# FLK01B.net
KiCad netlist of a schematic drawn in EAGLE
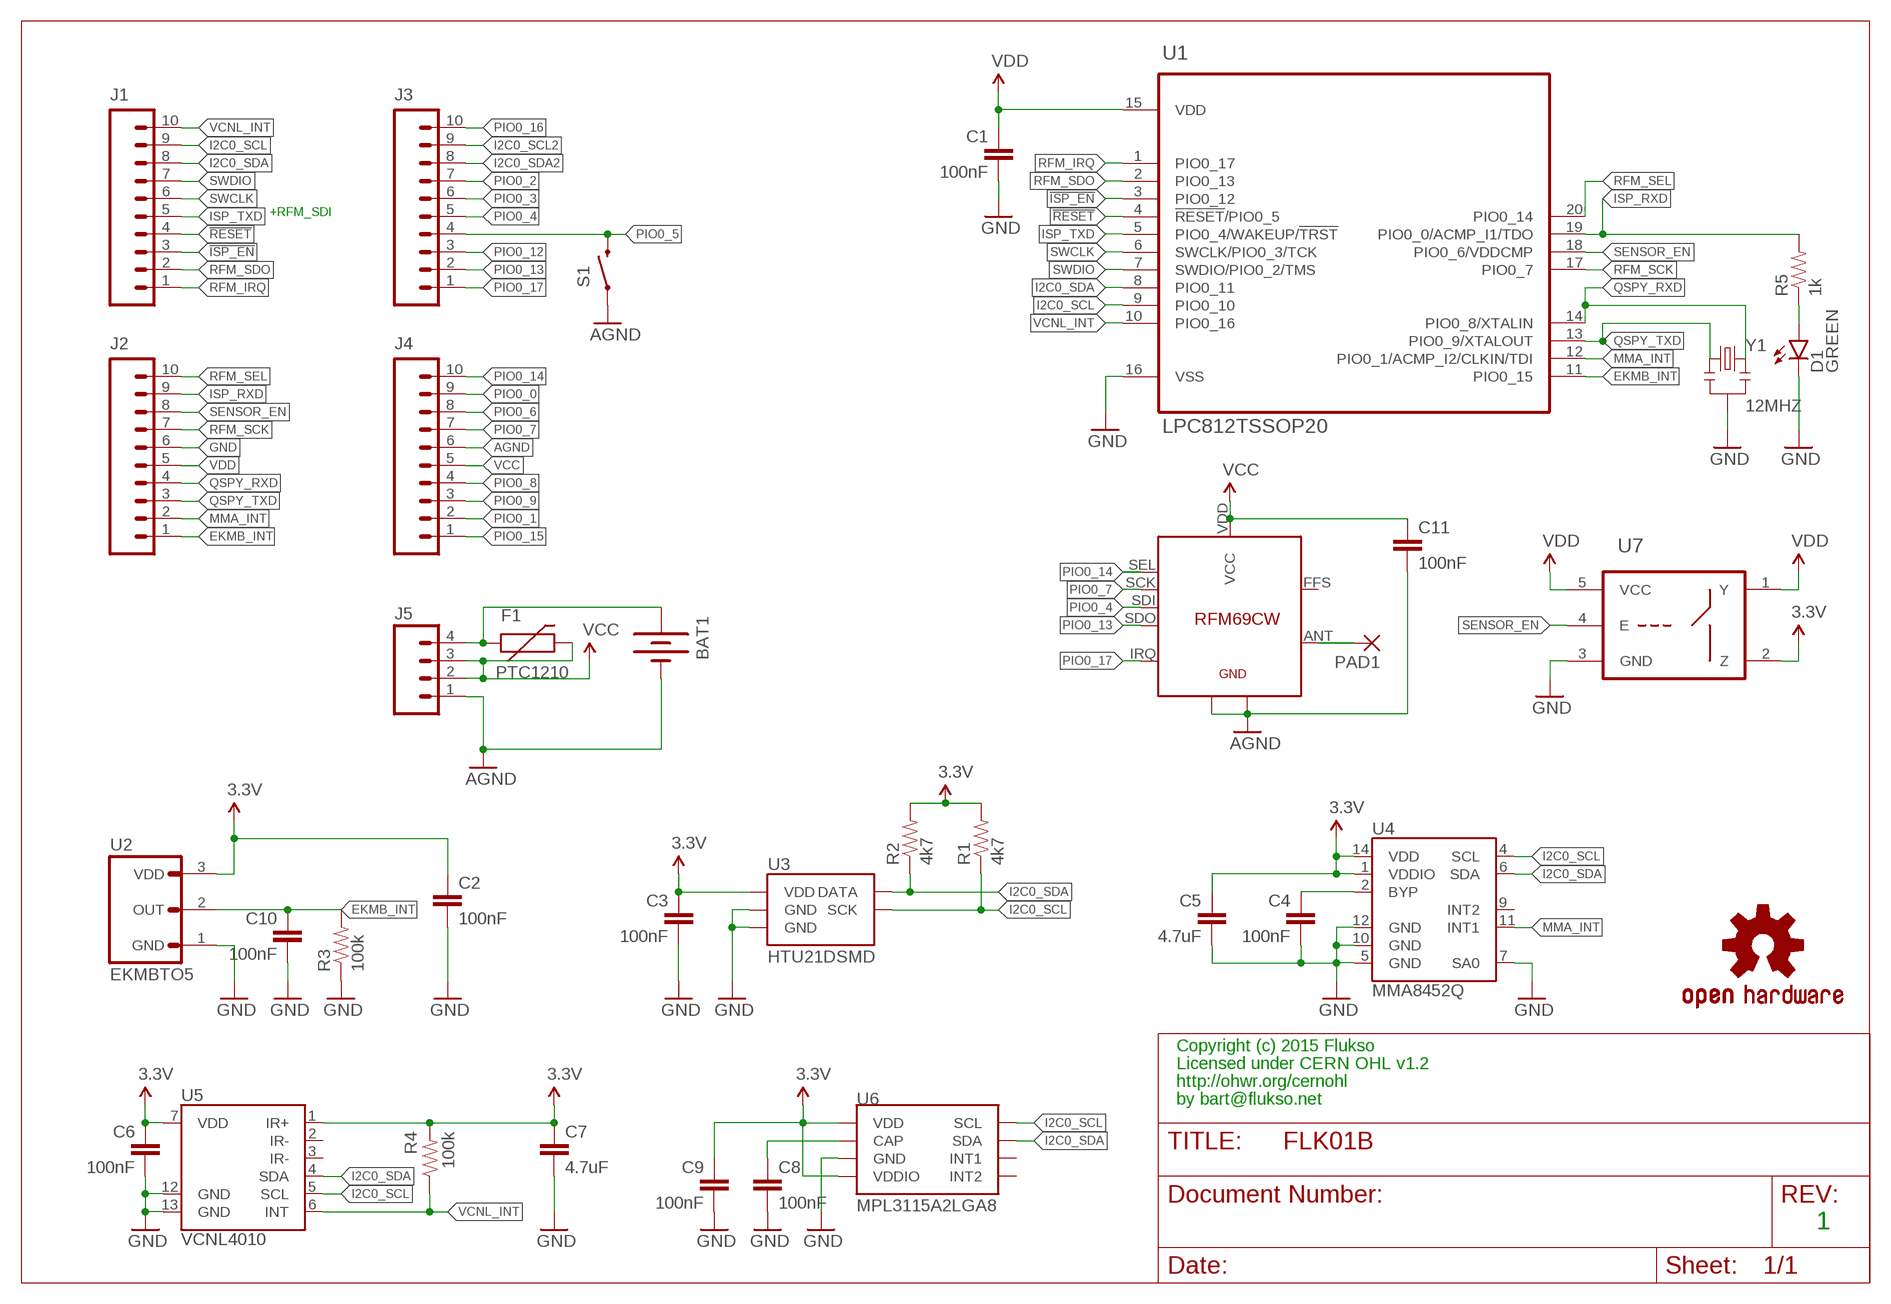
[diagram p0: schematic, sheet 1]

(export (version "E")
  (design (tool "Eeschema 10.0.6"))
  (components
    (comp (ref "BAT1")
      (value "BATTERY245PTH")
      (footprint "eagle-import:BATTCON_245MM_PTH")
      (libsource (lib "eagle-import") (part "BATTERY245PTH"))
    )
    (comp (ref "C1")
      (value "100nF")
      (footprint "eagle-import:0402-CAP")
      (libsource (lib "eagle-import") (part "CAP0402-CAP"))
    )
    (comp (ref "C2")
      (value "100nF")
      (footprint "eagle-import:0402-CAP")
      (libsource (lib "eagle-import") (part "CAP0402-CAP"))
    )
    (comp (ref "C3")
      (value "100nF")
      (footprint "eagle-import:0402-CAP")
      (libsource (lib "eagle-import") (part "CAP0402-CAP"))
    )
    (comp (ref "C4")
      (value "100nF")
      (footprint "eagle-import:0402-CAP")
      (libsource (lib "eagle-import") (part "CAP0402-CAP"))
    )
    (comp (ref "C5")
      (value "4.7uF")
      (footprint "eagle-import:C0805K")
      (libsource (lib "eagle-import") (part "CAP0805-CAP"))
    )
    (comp (ref "C6")
      (value "100nF")
      (footprint "eagle-import:0402-CAP")
      (libsource (lib "eagle-import") (part "CAP0402-CAP"))
    )
    (comp (ref "C7")
      (value "4.7uF")
      (footprint "eagle-import:C0805K")
      (libsource (lib "eagle-import") (part "CAP0805-CAP"))
    )
    (comp (ref "C8")
      (value "100nF")
      (footprint "eagle-import:0402-CAP")
      (libsource (lib "eagle-import") (part "CAP0402-CAP"))
    )
    (comp (ref "C9")
      (value "100nF")
      (footprint "eagle-import:0402-CAP")
      (libsource (lib "eagle-import") (part "CAP0402-CAP"))
    )
    (comp (ref "C10")
      (value "100nF")
      (footprint "eagle-import:0402-CAP")
      (libsource (lib "eagle-import") (part "CAP0402-CAP"))
    )
    (comp (ref "C11")
      (value "100nF")
      (footprint "eagle-import:0402-CAP")
      (libsource (lib "eagle-import") (part "sparkFun_CAP0402-CAP"))
    )
    (comp (ref "D1")
      (value "GREEN")
      (footprint "eagle-import:LED-0603")
      (libsource (lib "eagle-import") (part "LED-GREEN0603"))
    )
    (comp (ref "F1")
      (value "PTC1210")
      (footprint "eagle-import:1210")
      (libsource (lib "eagle-import") (part "PTC1210"))
    )
    (comp (ref "J1")
      (value "M10SMD_MALE_SHORT")
      (footprint "eagle-import:1X10_SMD_MALE_SHORT")
      (libsource (lib "eagle-import") (part "M10SMD_MALE_SHORT"))
    )
    (comp (ref "J2")
      (value "M10SMD_MALE_SHORT")
      (footprint "eagle-import:1X10_SMD_MALE_SHORT")
      (libsource (lib "eagle-import") (part "M10SMD_MALE_SHORT"))
    )
    (comp (ref "J3")
      (value "M10SMD_FEMALE_SHORT")
      (footprint "eagle-import:1X10_SMD_FEMALE_SHORT")
      (libsource (lib "eagle-import") (part "M10SMD_FEMALE_SHORT"))
    )
    (comp (ref "J4")
      (value "M10SMD_FEMALE_SHORT")
      (footprint "eagle-import:1X10_SMD_FEMALE_SHORT")
      (libsource (lib "eagle-import") (part "M10SMD_FEMALE_SHORT"))
    )
    (comp (ref "J5")
      (value "M041X04_NO_SILK")
      (footprint "eagle-import:1X04_NO_SILK")
      (libsource (lib "eagle-import") (part "M041X04_NO_SILK"))
    )
    (comp (ref "PAD1")
      (value "WIREPAD_1,6/0,8")
      (footprint "eagle-import:WIREPAD_1,6_0,8")
      (libsource (lib "eagle-import") (part "WIREPAD_1,6/0,8"))
    )
    (comp (ref "R1")
      (value "4k7")
      (footprint "eagle-import:0402-RES")
      (libsource (lib "eagle-import") (part "RESISTOR0402-RES"))
    )
    (comp (ref "R2")
      (value "4k7")
      (footprint "eagle-import:0402-RES")
      (libsource (lib "eagle-import") (part "RESISTOR0402-RES"))
    )
    (comp (ref "R3")
      (value "100k")
      (footprint "eagle-import:0402-RES")
      (libsource (lib "eagle-import") (part "RESISTOR0402-RES"))
    )
    (comp (ref "R4")
      (value "100k")
      (footprint "eagle-import:0402-RES")
      (libsource (lib "eagle-import") (part "RESISTOR0402-RES"))
    )
    (comp (ref "R5")
      (value "1k")
      (footprint "eagle-import:0402-RES")
      (libsource (lib "eagle-import") (part "RESISTOR0402-RES"))
    )
    (comp (ref "S1")
      (value "SWITCH-MOMENTARY-2SMD")
      (footprint "eagle-import:TACTILE_SWITCH_SMD")
      (libsource (lib "eagle-import") (part "SWITCH-MOMENTARY-2SMD"))
    )
    (comp (ref "U$3")
      (value "RFM69CW")
      (footprint "eagle-import:RFM69CW")
      (libsource (lib "eagle-import") (part "RFM69CW"))
    )
    (comp (ref "U$7")
      (value "OSHW-LOGOS")
      (footprint "eagle-import:OSHW-LOGO-S")
      (libsource (lib "eagle-import") (part "OSHW-LOGOS"))
    )
    (comp (ref "U1")
      (value "LPC812TSSOP20")
      (footprint "eagle-import:TSSOP20")
      (libsource (lib "eagle-import") (part "LPC812TSSOP20"))
    )
    (comp (ref "U2")
      (value "EKMBTO5")
      (footprint "eagle-import:TO5")
      (libsource (lib "eagle-import") (part "EKMBTO5"))
    )
    (comp (ref "U3")
      (value "HTU21DSMD")
      (footprint "eagle-import:HTU21D")
      (libsource (lib "eagle-import") (part "HTU21DSMD"))
    )
    (comp (ref "U4")
      (value "MMA8452Q")
      (footprint "eagle-import:QFN-16_0.5MM")
      (libsource (lib "eagle-import") (part "MMA8452Q"))
    )
    (comp (ref "U5")
      (value "VCNL4010")
      (footprint "eagle-import:VCNL4010")
      (libsource (lib "eagle-import") (part "VCNL4010"))
    )
    (comp (ref "U6")
      (value "MPL3115A2LGA8")
      (footprint "eagle-import:LGA8")
      (libsource (lib "eagle-import") (part "MPL3115A2LGA8"))
    )
    (comp (ref "U7")
      (value "741G66")
      (footprint "eagle-import:SOT353")
      (libsource (lib "eagle-import") (part "741G66"))
    )
    (comp (ref "Y1")
      (value "12MHZ")
      (footprint "eagle-import:RESONATOR-SMD")
      (libsource (lib "eagle-import") (part "RESONATOR8MHZ"))
    )
  )
  (nets
    (net (code "1") (name "/~{ISP_EN}") (class "Default")
      (node (ref "J1") (pin "3") (pinfunction "3_3") (pintype "passive"))
      (node (ref "U1") (pin "3") (pinfunction "PIO0_12_3") (pintype "bidirectional"))
    )
    (net (code "2") (name "/~{RESET}") (class "Default")
      (node (ref "J1") (pin "4") (pinfunction "4_4") (pintype "passive"))
      (node (ref "U1") (pin "4") (pinfunction "~{RESET}/PIO0_5_4") (pintype "bidirectional"))
    )
    (net (code "3") (name "3.3V") (class "Default")
      (node (ref "C2") (pin "1") (pinfunction "1_1") (pintype "passive"))
      (node (ref "C3") (pin "1") (pinfunction "1_1") (pintype "passive"))
      (node (ref "C5") (pin "1") (pinfunction "1_1") (pintype "passive"))
      (node (ref "C6") (pin "1") (pinfunction "1_1") (pintype "passive"))
      (node (ref "C7") (pin "1") (pinfunction "1_1") (pintype "passive"))
      (node (ref "C9") (pin "1") (pinfunction "1_1") (pintype "passive"))
      (node (ref "R1") (pin "2") (pinfunction "2_2") (pintype "passive"))
      (node (ref "R2") (pin "2") (pinfunction "2_2") (pintype "passive"))
      (node (ref "R4") (pin "2") (pinfunction "2_2") (pintype "passive"))
      (node (ref "U2") (pin "3") (pinfunction "VDD_3") (pintype "power_in"))
      (node (ref "U3") (pin "VDD") (pinfunction "VDD_VDD") (pintype "power_in"))
      (node (ref "U4") (pin "1") (pinfunction "VDDIO_1") (pintype "bidirectional"))
      (node (ref "U4") (pin "14") (pinfunction "VDD_14") (pintype "bidirectional"))
      (node (ref "U5") (pin "1") (pinfunction "IR+_1") (pintype "bidirectional"))
      (node (ref "U5") (pin "7") (pinfunction "VDD_7") (pintype "bidirectional"))
      (node (ref "U6") (pin "1") (pinfunction "VDD_1") (pintype "power_in"))
      (node (ref "U6") (pin "4") (pinfunction "VDDIO_4") (pintype "power_in"))
      (node (ref "U7") (pin "2") (pinfunction "Z_2") (pintype "bidirectional"))
    )
    (net (code "4") (name "AGND") (class "Default")
      (node (ref "BAT1") (pin "2") (pinfunction "-_2") (pintype "power_in"))
      (node (ref "C11") (pin "2") (pinfunction "2_2") (pintype "passive"))
      (node (ref "J4") (pin "6") (pinfunction "6_6") (pintype "passive"))
      (node (ref "J5") (pin "1") (pinfunction "1_1") (pintype "passive"))
      (node (ref "S1") (pin "1") (pinfunction "1_1") (pintype "passive"))
      (node (ref "U$3") (pin "GND1") (pinfunction "GND1_GND1") (pintype "power_in"))
      (node (ref "U$3") (pin "GND2") (pinfunction "GND2_GND2") (pintype "power_in"))
    )
    (net (code "5") (name "EKMB_INT") (class "Default")
      (node (ref "C10") (pin "1") (pinfunction "1_1") (pintype "passive"))
      (node (ref "J2") (pin "1") (pinfunction "1_1") (pintype "passive"))
      (node (ref "R3") (pin "2") (pinfunction "2_2") (pintype "passive"))
      (node (ref "U1") (pin "11") (pinfunction "PIO0_15_11") (pintype "bidirectional"))
      (node (ref "U2") (pin "2") (pinfunction "OUT_2") (pintype "output"))
    )
    (net (code "6") (name "GND") (class "Default")
      (node (ref "C1") (pin "2") (pinfunction "2_2") (pintype "passive"))
      (node (ref "C10") (pin "2") (pinfunction "2_2") (pintype "passive"))
      (node (ref "C2") (pin "2") (pinfunction "2_2") (pintype "passive"))
      (node (ref "C3") (pin "2") (pinfunction "2_2") (pintype "passive"))
      (node (ref "C4") (pin "2") (pinfunction "2_2") (pintype "passive"))
      (node (ref "C5") (pin "2") (pinfunction "2_2") (pintype "passive"))
      (node (ref "C6") (pin "2") (pinfunction "2_2") (pintype "passive"))
      (node (ref "C7") (pin "2") (pinfunction "2_2") (pintype "passive"))
      (node (ref "C8") (pin "2") (pinfunction "2_2") (pintype "passive"))
      (node (ref "C9") (pin "2") (pinfunction "2_2") (pintype "passive"))
      (node (ref "D1") (pin "C") (pinfunction "C_C") (pintype "passive"))
      (node (ref "J2") (pin "6") (pinfunction "6_6") (pintype "passive"))
      (node (ref "R3") (pin "1") (pinfunction "1_1") (pintype "passive"))
      (node (ref "U1") (pin "16") (pinfunction "VSS_16") (pintype "power_in"))
      (node (ref "U2") (pin "1") (pinfunction "GND_1") (pintype "power_in"))
      (node (ref "U3") (pin "7") (pinfunction "GND_7") (pintype "power_in"))
      (node (ref "U3") (pin "GND") (pinfunction "GND_GND") (pintype "power_in"))
      (node (ref "U4") (pin "10") (pinfunction "GND_10") (pintype "bidirectional"))
      (node (ref "U4") (pin "12") (pinfunction "GND_12") (pintype "bidirectional"))
      (node (ref "U4") (pin "5") (pinfunction "GND_5") (pintype "bidirectional"))
      (node (ref "U4") (pin "7") (pinfunction "SA0_7") (pintype "bidirectional"))
      (node (ref "U5") (pin "12") (pinfunction "GND_12") (pintype "bidirectional"))
      (node (ref "U5") (pin "13") (pinfunction "GND_13") (pintype "bidirectional"))
      (node (ref "U6") (pin "3") (pinfunction "GND_3") (pintype "power_in"))
      (node (ref "U7") (pin "3") (pinfunction "GND_3") (pintype "passive"))
      (node (ref "Y1") (pin "2") (pinfunction "2_2") (pintype "passive"))
    )
    (net (code "7") (name "I2C0_SCL") (class "Default")
      (node (ref "J1") (pin "9") (pinfunction "9_9") (pintype "passive"))
      (node (ref "R1") (pin "1") (pinfunction "1_1") (pintype "passive"))
      (node (ref "U1") (pin "9") (pinfunction "PIO0_10_9") (pintype "input"))
      (node (ref "U3") (pin "SCK") (pinfunction "SCK_SCK") (pintype "input"))
      (node (ref "U4") (pin "4") (pinfunction "SCL_4") (pintype "bidirectional"))
      (node (ref "U5") (pin "5") (pinfunction "SCL_5") (pintype "bidirectional"))
      (node (ref "U6") (pin "8") (pinfunction "SCL_8") (pintype "bidirectional"))
    )
    (net (code "8") (name "I2C0_SCL2") (class "Default")
      (node (ref "J3") (pin "9") (pinfunction "9_9") (pintype "passive"))
    )
    (net (code "9") (name "I2C0_SDA") (class "Default")
      (node (ref "J1") (pin "8") (pinfunction "8_8") (pintype "passive"))
      (node (ref "R2") (pin "1") (pinfunction "1_1") (pintype "passive"))
      (node (ref "U1") (pin "8") (pinfunction "PIO0_11_8") (pintype "input"))
      (node (ref "U3") (pin "DATA") (pinfunction "DATA_DATA") (pintype "bidirectional"))
      (node (ref "U4") (pin "6") (pinfunction "SDA_6") (pintype "bidirectional"))
      (node (ref "U5") (pin "4") (pinfunction "SDA_4") (pintype "bidirectional"))
      (node (ref "U6") (pin "7") (pinfunction "SDA_7") (pintype "bidirectional"))
    )
    (net (code "10") (name "I2C0_SDA2") (class "Default")
      (node (ref "J3") (pin "8") (pinfunction "8_8") (pintype "passive"))
    )
    (net (code "11") (name "ISP_RXD") (class "Default")
      (node (ref "J2") (pin "9") (pinfunction "9_9") (pintype "passive"))
      (node (ref "R5") (pin "2") (pinfunction "2_2") (pintype "passive"))
      (node (ref "U1") (pin "19") (pinfunction "PIO0_0/ACMP_I1/TDO_19") (pintype "bidirectional"))
    )
    (net (code "12") (name "ISP_TXD") (class "Default")
      (node (ref "J1") (pin "5") (pinfunction "5_5") (pintype "passive"))
      (node (ref "U1") (pin "5") (pinfunction "PIO0_4/WAKEUP/~{TRST}_5") (pintype "bidirectional"))
    )
    (net (code "13") (name "MMA_INT") (class "Default")
      (node (ref "J2") (pin "2") (pinfunction "2_2") (pintype "passive"))
      (node (ref "U1") (pin "12") (pinfunction "PIO0_1/ACMP_I2/CLKIN/TDI_12") (pintype "bidirectional"))
      (node (ref "U4") (pin "11") (pinfunction "INT1_11") (pintype "bidirectional"))
    )
    (net (code "14") (name "Net-(BAT1-+)") (class "Default")
      (node (ref "BAT1") (pin "3") (pinfunction "+_3") (pintype "power_in"))
      (node (ref "F1") (pin "1") (pinfunction "1_1") (pintype "bidirectional"))
      (node (ref "J5") (pin "4") (pinfunction "4_4") (pintype "passive"))
    )
    (net (code "15") (name "Net-(D1-PadA)") (class "Default")
      (node (ref "D1") (pin "A") (pinfunction "A_A") (pintype "passive"))
      (node (ref "R5") (pin "1") (pinfunction "1_1") (pintype "passive"))
    )
    (net (code "16") (name "Net-(PAD1-P)") (class "Default")
      (node (ref "PAD1") (pin "1") (pinfunction "P_1") (pintype "passive"))
      (node (ref "U$3") (pin "ANT") (pinfunction "ANT_ANT") (pintype "passive"))
    )
    (net (code "17") (name "Net-(U4-BYP)") (class "Default")
      (node (ref "C4") (pin "1") (pinfunction "1_1") (pintype "passive"))
      (node (ref "U4") (pin "2") (pinfunction "BYP_2") (pintype "bidirectional"))
    )
    (net (code "18") (name "Net-(U6-CAP)") (class "Default")
      (node (ref "C8") (pin "1") (pinfunction "1_1") (pintype "passive"))
      (node (ref "U6") (pin "2") (pinfunction "CAP_2") (pintype "power_in"))
    )
    (net (code "19") (name "PIO0_0") (class "Default")
      (node (ref "J4") (pin "9") (pinfunction "9_9") (pintype "passive"))
    )
    (net (code "20") (name "PIO0_1") (class "Default")
      (node (ref "J4") (pin "2") (pinfunction "2_2") (pintype "passive"))
    )
    (net (code "21") (name "PIO0_2") (class "Default")
      (node (ref "J3") (pin "7") (pinfunction "7_7") (pintype "passive"))
    )
    (net (code "22") (name "PIO0_3") (class "Default")
      (node (ref "J3") (pin "6") (pinfunction "6_6") (pintype "passive"))
    )
    (net (code "23") (name "PIO0_4") (class "Default")
      (node (ref "J3") (pin "5") (pinfunction "5_5") (pintype "passive"))
      (node (ref "U$3") (pin "SDI") (pinfunction "SDI_SDI") (pintype "input"))
    )
    (net (code "24") (name "PIO0_5") (class "Default")
      (node (ref "J3") (pin "4") (pinfunction "4_4") (pintype "passive"))
      (node (ref "S1") (pin "3") (pinfunction "2_3") (pintype "passive"))
    )
    (net (code "25") (name "PIO0_6") (class "Default")
      (node (ref "J4") (pin "8") (pinfunction "8_8") (pintype "passive"))
    )
    (net (code "26") (name "PIO0_7") (class "Default")
      (node (ref "J4") (pin "7") (pinfunction "7_7") (pintype "passive"))
      (node (ref "U$3") (pin "SCK") (pinfunction "SCK_SCK") (pintype "input"))
    )
    (net (code "27") (name "PIO0_8") (class "Default")
      (node (ref "J4") (pin "4") (pinfunction "4_4") (pintype "passive"))
    )
    (net (code "28") (name "PIO0_9") (class "Default")
      (node (ref "J4") (pin "3") (pinfunction "3_3") (pintype "passive"))
    )
    (net (code "29") (name "PIO0_12") (class "Default")
      (node (ref "J3") (pin "3") (pinfunction "3_3") (pintype "passive"))
    )
    (net (code "30") (name "PIO0_13") (class "Default")
      (node (ref "J3") (pin "2") (pinfunction "2_2") (pintype "passive"))
      (node (ref "U$3") (pin "SDO") (pinfunction "SDO_SDO") (pintype "output"))
    )
    (net (code "31") (name "PIO0_14") (class "Default")
      (node (ref "J4") (pin "10") (pinfunction "10_10") (pintype "passive"))
      (node (ref "U$3") (pin "SEL") (pinfunction "SEL_SEL") (pintype "input"))
    )
    (net (code "32") (name "PIO0_15") (class "Default")
      (node (ref "J4") (pin "1") (pinfunction "1_1") (pintype "passive"))
    )
    (net (code "33") (name "PIO0_16") (class "Default")
      (node (ref "J3") (pin "10") (pinfunction "10_10") (pintype "passive"))
    )
    (net (code "34") (name "PIO0_17") (class "Default")
      (node (ref "J3") (pin "1") (pinfunction "1_1") (pintype "passive"))
      (node (ref "U$3") (pin "IRQ") (pinfunction "IRQ_IRQ") (pintype "open_collector"))
    )
    (net (code "35") (name "QSPY_RXD") (class "Default")
      (node (ref "J2") (pin "4") (pinfunction "4_4") (pintype "passive"))
      (node (ref "U1") (pin "14") (pinfunction "PIO0_8/XTALIN_14") (pintype "bidirectional"))
      (node (ref "Y1") (pin "3") (pinfunction "3_3") (pintype "passive"))
    )
    (net (code "36") (name "QSPY_TXD") (class "Default")
      (node (ref "J2") (pin "3") (pinfunction "3_3") (pintype "passive"))
      (node (ref "U1") (pin "13") (pinfunction "PIO0_9/XTALOUT_13") (pintype "bidirectional"))
      (node (ref "Y1") (pin "1") (pinfunction "1_1") (pintype "passive"))
    )
    (net (code "37") (name "RFM_IRQ") (class "Default")
      (node (ref "J1") (pin "1") (pinfunction "1_1") (pintype "passive"))
      (node (ref "U1") (pin "1") (pinfunction "PIO0_17_1") (pintype "bidirectional"))
    )
    (net (code "38") (name "RFM_SCK") (class "Default")
      (node (ref "J2") (pin "7") (pinfunction "7_7") (pintype "passive"))
      (node (ref "U1") (pin "17") (pinfunction "PIO0_7_17") (pintype "bidirectional"))
    )
    (net (code "39") (name "RFM_SDO") (class "Default")
      (node (ref "J1") (pin "2") (pinfunction "2_2") (pintype "passive"))
      (node (ref "U1") (pin "2") (pinfunction "PIO0_13_2") (pintype "bidirectional"))
    )
    (net (code "40") (name "RFM_SEL") (class "Default")
      (node (ref "J2") (pin "10") (pinfunction "10_10") (pintype "passive"))
      (node (ref "U1") (pin "20") (pinfunction "PIO0_14_20") (pintype "bidirectional"))
    )
    (net (code "41") (name "SENSOR_EN") (class "Default")
      (node (ref "J2") (pin "8") (pinfunction "8_8") (pintype "passive"))
      (node (ref "U1") (pin "18") (pinfunction "PIO0_6/VDDCMP_18") (pintype "bidirectional"))
      (node (ref "U7") (pin "4") (pinfunction "E_4") (pintype "input"))
    )
    (net (code "42") (name "SWCLK") (class "Default")
      (node (ref "J1") (pin "6") (pinfunction "6_6") (pintype "passive"))
      (node (ref "U1") (pin "6") (pinfunction "SWCLK/PIO0_3/TCK_6") (pintype "bidirectional"))
    )
    (net (code "43") (name "SWDIO") (class "Default")
      (node (ref "J1") (pin "7") (pinfunction "7_7") (pintype "passive"))
      (node (ref "U1") (pin "7") (pinfunction "SWDIO/PIO0_2/TMS_7") (pintype "bidirectional"))
    )
    (net (code "44") (name "VCC") (class "Default")
      (node (ref "C11") (pin "1") (pinfunction "1_1") (pintype "passive"))
      (node (ref "F1") (pin "2") (pinfunction "2_2") (pintype "bidirectional"))
      (node (ref "J4") (pin "5") (pinfunction "5_5") (pintype "passive"))
      (node (ref "J5") (pin "2") (pinfunction "2_2") (pintype "passive"))
      (node (ref "J5") (pin "3") (pinfunction "3_3") (pintype "passive"))
      (node (ref "U$3") (pin "VDD") (pinfunction "VCC_VDD") (pintype "power_in"))
    )
    (net (code "45") (name "VCNL_INT") (class "Default")
      (node (ref "J1") (pin "10") (pinfunction "10_10") (pintype "passive"))
      (node (ref "R4") (pin "1") (pinfunction "1_1") (pintype "passive"))
      (node (ref "U1") (pin "10") (pinfunction "PIO0_16_10") (pintype "bidirectional"))
      (node (ref "U5") (pin "6") (pinfunction "INT_6") (pintype "bidirectional"))
    )
    (net (code "46") (name "VDD") (class "Default")
      (node (ref "C1") (pin "1") (pinfunction "1_1") (pintype "passive"))
      (node (ref "J2") (pin "5") (pinfunction "5_5") (pintype "passive"))
      (node (ref "U1") (pin "15") (pinfunction "VDD_15") (pintype "power_in"))
      (node (ref "U7") (pin "1") (pinfunction "Y_1") (pintype "bidirectional"))
      (node (ref "U7") (pin "5") (pinfunction "VCC_5") (pintype "power_in"))
    )
    (net (code "47") (name "unconnected-(U$3-PadFFS)") (class "Default")
      (node (ref "U$3") (pin "FFS") (pinfunction "FFS_FFS") (pintype "bidirectional"))
    )
    (net (code "48") (name "unconnected-(U4-INT2-Pad9)") (class "Default")
      (node (ref "U4") (pin "9") (pinfunction "INT2_9") (pintype "bidirectional"))
    )
    (net (code "49") (name "unconnected-(U5-IR--Pad2)") (class "Default")
      (node (ref "U5") (pin "2") (pinfunction "IR-_2") (pintype "bidirectional"))
    )
    (net (code "50") (name "unconnected-(U5-IR--Pad3)") (class "Default")
      (node (ref "U5") (pin "3") (pinfunction "IR-_3") (pintype "bidirectional"))
    )
    (net (code "51") (name "unconnected-(U6-INT1-Pad6)") (class "Default")
      (node (ref "U6") (pin "6") (pinfunction "INT1_6") (pintype "output"))
    )
    (net (code "52") (name "unconnected-(U6-INT2-Pad5)") (class "Default")
      (node (ref "U6") (pin "5") (pinfunction "INT2_5") (pintype "output"))
    )
  )
)
